# 12_B_TO_B.net
KiCad netlist of a schematic drawn in Altium Designer
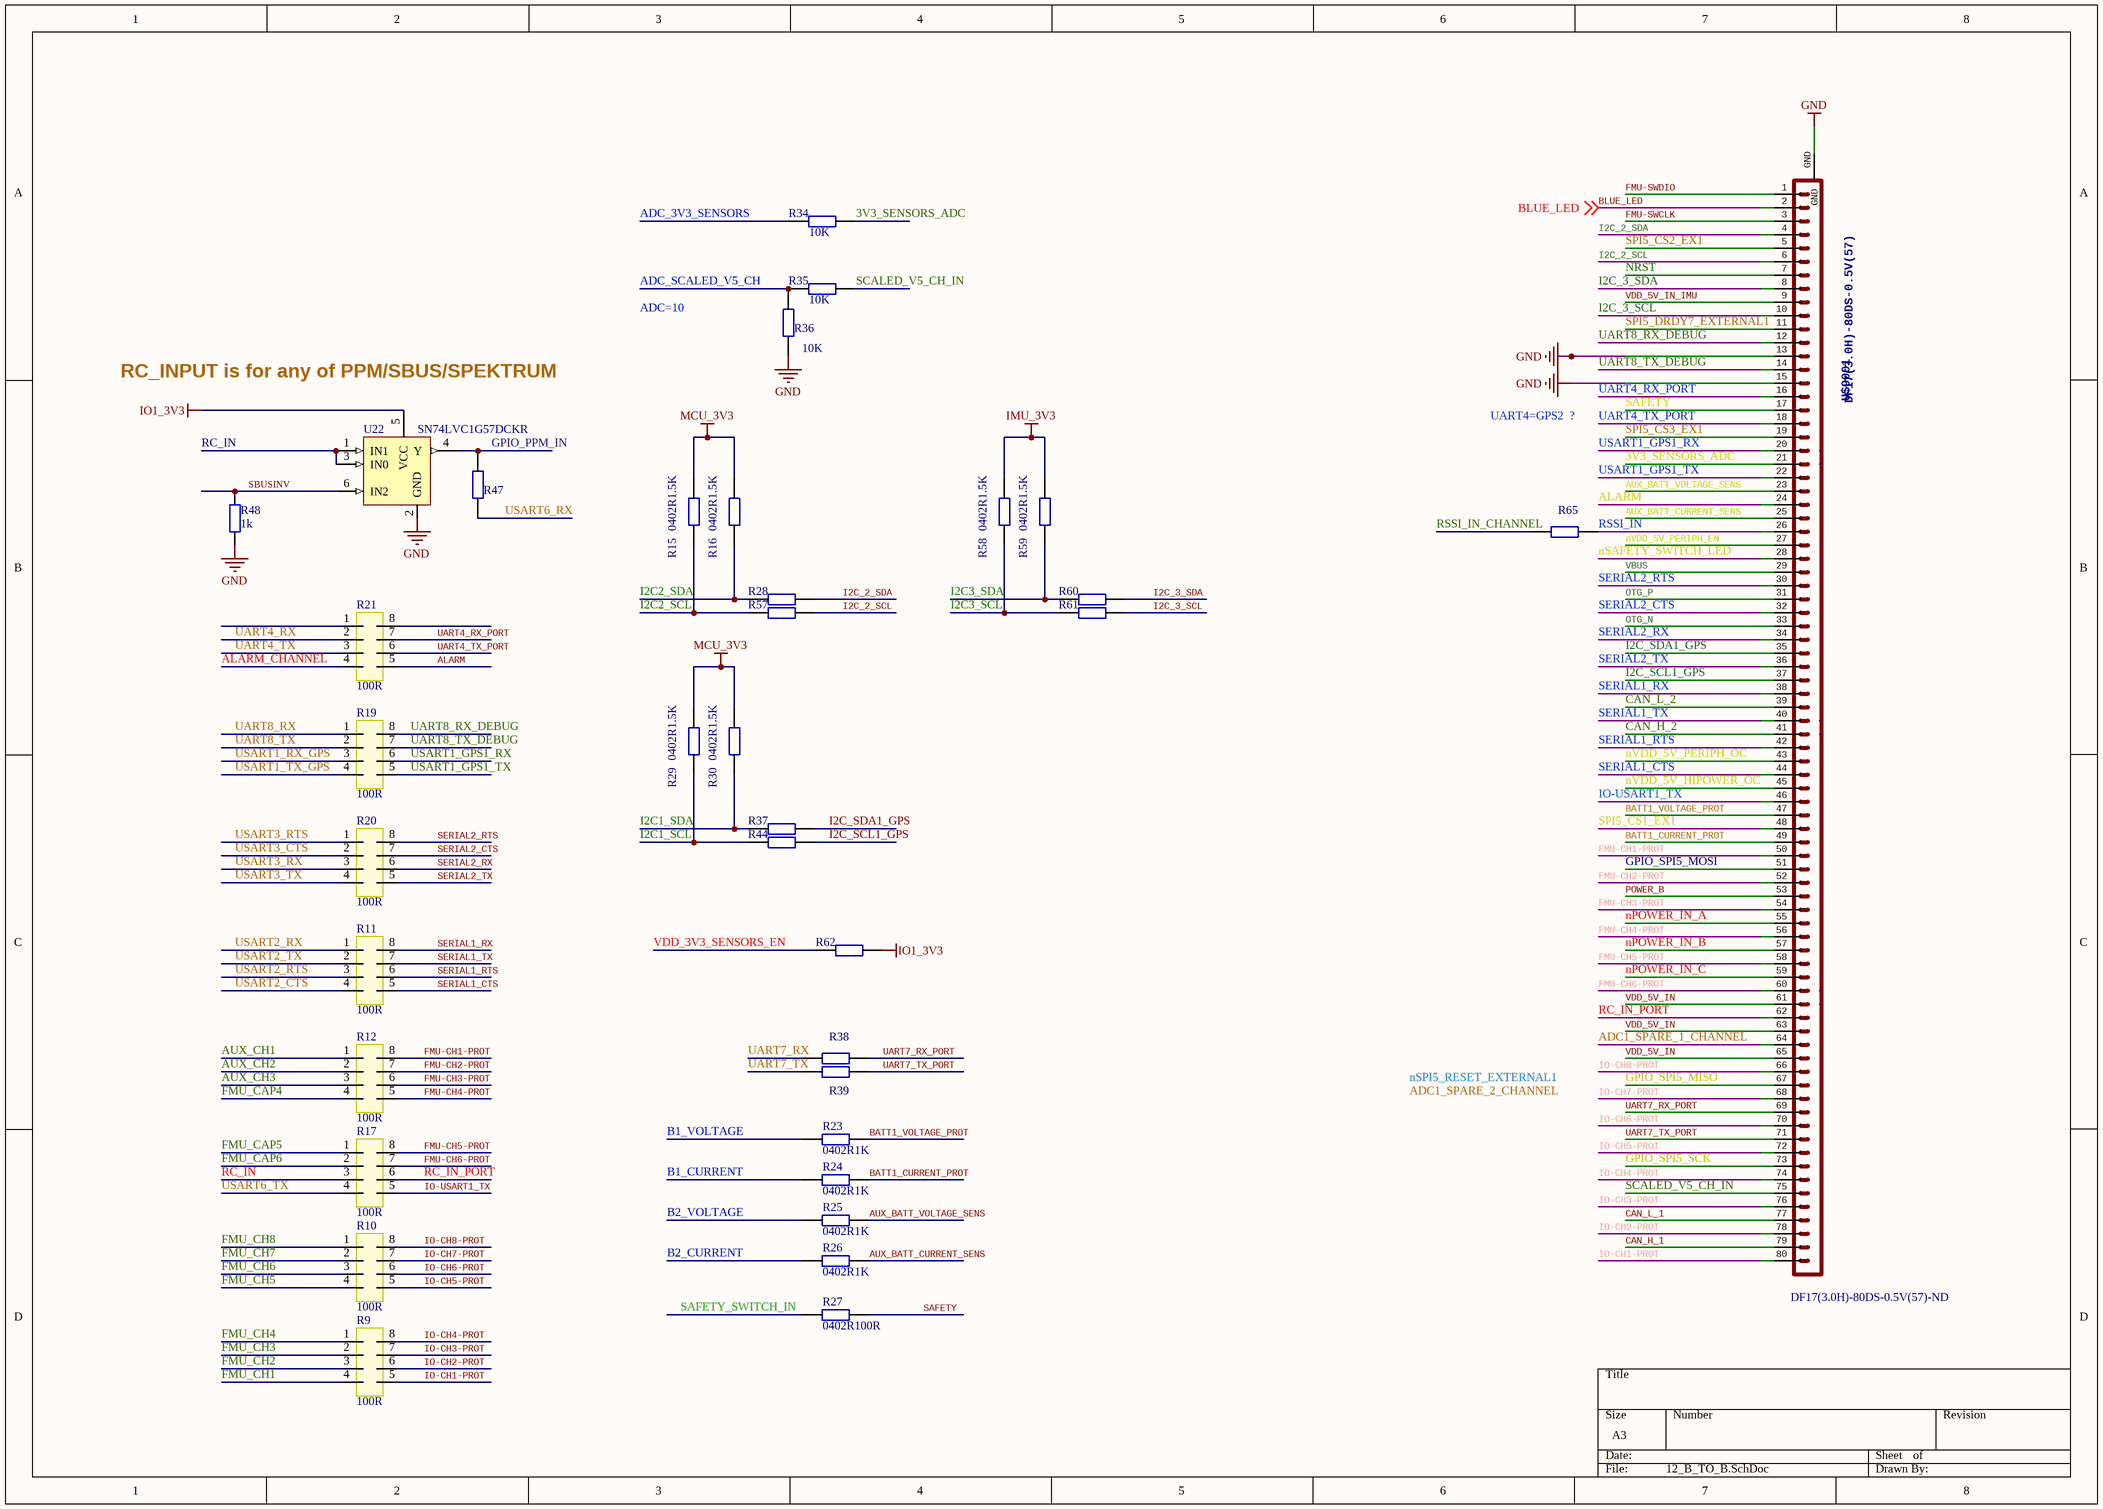
[diagram p0: 12_B_TO_B.SchDoc]

(export (version "E")
  (design (tool "Eeschema 10.0.6"))
  (components
    (comp (ref "R9") (value "100R") (footprint "0402_4r") (libsource (lib "CUAV") (part "0402-8R-4R")))
    (comp (ref "R10") (value "100R") (footprint "0402_4r") (libsource (lib "CUAV") (part "0402-8R-4R")))
    (comp (ref "R11") (value "100R") (footprint "0402_4r") (libsource (lib "CUAV") (part "0402-8R-4R")))
    (comp (ref "R12") (value "100R") (footprint "0402_4r") (libsource (lib "CUAV") (part "0402-8R-4R")))
    (comp (ref "R15")
      (value "0402R1.5K")
      (footprint "0402R")
      (description "0402R10K 1%")
      (libsource (lib "CUAV") (part "0402R10K"))
    )
    (comp (ref "R16")
      (value "0402R1.5K")
      (footprint "0402R")
      (description "0402R10K 1%")
      (libsource (lib "CUAV") (part "0402R10K"))
    )
    (comp (ref "R17") (value "100R") (footprint "0402_4r") (libsource (lib "CUAV") (part "0402-8R-4R")))
    (comp (ref "R19") (value "100R") (footprint "0402_4r") (libsource (lib "CUAV") (part "0402-8R-4R")))
    (comp (ref "R20") (value "100R") (footprint "0402_4r") (libsource (lib "CUAV") (part "0402-8R-4R")))
    (comp (ref "R21") (value "100R") (footprint "0402_4r") (libsource (lib "CUAV") (part "0402-8R-4R")))
    (comp (ref "R23")
      (value "0402R1K")
      (footprint "0402R")
      (description "0402R100R 1%")
      (libsource (lib "CUAV") (part "0402R100R"))
    )
    (comp (ref "R24")
      (value "0402R1K")
      (footprint "0402R")
      (description "0402R100R 1%")
      (libsource (lib "CUAV") (part "0402R100R"))
    )
    (comp (ref "R25")
      (value "0402R1K")
      (footprint "0402R")
      (description "0402R100R 1%")
      (libsource (lib "CUAV") (part "0402R100R"))
    )
    (comp (ref "R26")
      (value "0402R1K")
      (footprint "0402R")
      (description "0402R100R 1%")
      (libsource (lib "CUAV") (part "0402R100R"))
    )
    (comp (ref "R27")
      (value "0402R100R")
      (footprint "0402R")
      (description "0402R100R 1%")
      (libsource (lib "CUAV") (part "0402R100R"))
    )
    (comp (ref "R28")
      (value "0402R100R")
      (footprint "0402R")
      (description "0402R100R 1%")
      (libsource (lib "CUAV") (part "0402R100R"))
    )
    (comp (ref "R29")
      (value "0402R1.5K")
      (footprint "0402R")
      (description "0402R10K 1%")
      (libsource (lib "CUAV") (part "0402R10K"))
    )
    (comp (ref "R30")
      (value "0402R1.5K")
      (footprint "0402R")
      (description "0402R10K 1%")
      (libsource (lib "CUAV") (part "0402R10K"))
    )
    (comp (ref "R34")
      (value "10K")
      (footprint "0402R")
      (description "0402R100R 1%")
      (libsource (lib "CUAV") (part "0402R100R"))
    )
    (comp (ref "R35")
      (value "10K")
      (footprint "0402R")
      (description "0402R100R 1%")
      (libsource (lib "CUAV") (part "0402R100R"))
    )
    (comp (ref "R36")
      (value "10K")
      (footprint "0402R")
      (description "0402R100R 1%")
      (libsource (lib "") (part "0402R100R_1"))
    )
    (comp (ref "R37")
      (value "0402R100R")
      (footprint "0402R")
      (description "0402R100R 1%")
      (libsource (lib "CUAV") (part "0402R100R"))
    )
    (comp (ref "R38")
      (value "0402R100R")
      (footprint "0402R")
      (description "0402R100R 1%")
      (libsource (lib "CUAV") (part "0402R100R"))
    )
    (comp (ref "R39")
      (value "0402R100R")
      (footprint "0402R")
      (description "0402R100R 1%")
      (libsource (lib "CUAV") (part "0402R100R"))
    )
    (comp (ref "R44")
      (value "0402R100R")
      (footprint "0402R")
      (description "0402R100R 1%")
      (libsource (lib "CUAV") (part "0402R100R"))
    )
    (comp (ref "R47")
      (value "100R")
      (footprint "0402R")
      (description "0402R100R 1%")
      (libsource (lib "") (part "0402R100R_1"))
    )
    (comp (ref "R48")
      (value "1k")
      (description "Resistor")
      (fields (field (name "PUBLISHER") "Altium Limited"))
      (libsource (lib "Miscellaneous Devices") (part "Res2"))
    )
    (comp (ref "R57")
      (value "0402R100R")
      (footprint "0402R")
      (description "0402R100R 1%")
      (libsource (lib "CUAV") (part "0402R100R"))
    )
    (comp (ref "R58")
      (value "0402R1.5K")
      (footprint "0402R")
      (description "0402R10K 1%")
      (libsource (lib "CUAV") (part "0402R10K"))
    )
    (comp (ref "R59")
      (value "0402R1.5K")
      (footprint "0402R")
      (description "0402R10K 1%")
      (libsource (lib "CUAV") (part "0402R10K"))
    )
    (comp (ref "R60")
      (value "0402R100R")
      (footprint "0402R")
      (description "0402R100R 1%")
      (libsource (lib "CUAV") (part "0402R100R"))
    )
    (comp (ref "R61")
      (value "0402R100R")
      (footprint "0402R")
      (description "0402R100R 1%")
      (libsource (lib "CUAV") (part "0402R100R"))
    )
    (comp (ref "R62")
      (value "10K/NC")
      (footprint "0402R")
      (description "0402R100R 1%")
      (libsource (lib "CUAV") (part "0402R100R"))
    )
    (comp (ref "R65")
      (value "0402R100R")
      (footprint "0402R")
      (description "0402R100R 1%")
      (libsource (lib "CUAV") (part "0402R100R"))
    )
    (comp (ref "U$9001")
      (value "DF17(3.0H)-80DS-0.5V(57)")
      (footprint "DF17(3.0H)-80DS-0.5V(57)")
      (fields (field (name "SUPPLIER PART NUMBER 1") "DF17(3.0H)-80DS-0.5V(57)-ND"))
      (libsource (lib "altium-import") (part "root_0_CON-DF17-80F_"))
    )
    (comp (ref "U22")
      (value "SN74LVC1G57DCKR")
      (footprint "sot323-6")
      (libsource (lib "My_Altium") (part "74LVC1G57"))
    )
  )
  (nets
    (net (code "1") (name "/3V3_SENSORS_ADC") (class "Default")
      (node (ref "R34") (pin "2") (pintype "passive"))
      (node (ref "U$9001") (pin "21") (pinfunction "21_21") (pintype "passive"))
    )
    (net (code "2") (name "/ADC1_SPARE_1_CHANNEL") (class "Default")
      (node (ref "U$9001") (pin "64") (pinfunction "64_64") (pintype "passive"))
    )
    (net (code "5") (name "/ADC_3V3_SENSORS") (class "Default")
      (node (ref "R34") (pin "1") (pintype "passive"))
    )
    (net (code "6") (name "/ADC_SCALED_V5_CH") (class "Default")
      (node (ref "R35") (pin "1") (pintype "passive"))
      (node (ref "R36") (pin "2") (pintype "passive"))
    )
    (net (code "7") (name "/ALARM") (class "Default")
      (node (ref "R21") (pin "5") (pinfunction "5_5") (pintype "passive"))
      (node (ref "U$9001") (pin "24") (pinfunction "24_24") (pintype "passive"))
    )
    (net (code "8") (name "/ALARM_CHANNEL") (class "Default")
      (node (ref "R21") (pin "4") (pinfunction "4_4") (pintype "passive"))
    )
    (net (code "9") (name "/AUX_BATT_CURRENT_SENS") (class "Default")
      (node (ref "R26") (pin "2") (pintype "passive"))
      (node (ref "U$9001") (pin "25") (pinfunction "25_25") (pintype "passive"))
    )
    (net (code "10") (name "/AUX_BATT_VOLTAGE_SENS") (class "Default")
      (node (ref "R25") (pin "2") (pintype "passive"))
      (node (ref "U$9001") (pin "23") (pinfunction "23_23") (pintype "passive"))
    )
    (net (code "11") (name "/AUX_CH1") (class "Default")
      (node (ref "R12") (pin "1") (pinfunction "1_1") (pintype "passive"))
    )
    (net (code "12") (name "/AUX_CH2") (class "Default")
      (node (ref "R12") (pin "2") (pinfunction "2_2") (pintype "passive"))
    )
    (net (code "13") (name "/AUX_CH3") (class "Default")
      (node (ref "R12") (pin "3") (pinfunction "3_3") (pintype "passive"))
    )
    (net (code "14") (name "/B1_CURRENT") (class "Default") (node (ref "R24") (pin "1") (pintype "passive")))
    (net (code "15") (name "/B1_VOLTAGE") (class "Default") (node (ref "R23") (pin "1") (pintype "passive")))
    (net (code "16") (name "/B2_CURRENT") (class "Default") (node (ref "R26") (pin "1") (pintype "passive")))
    (net (code "17") (name "/B2_VOLTAGE") (class "Default") (node (ref "R25") (pin "1") (pintype "passive")))
    (net (code "18") (name "/BATT1_CURRENT_PROT") (class "Default")
      (node (ref "R24") (pin "2") (pintype "passive"))
      (node (ref "U$9001") (pin "49") (pinfunction "49_49") (pintype "passive"))
    )
    (net (code "19") (name "/BATT1_VOLTAGE_PROT") (class "Default")
      (node (ref "R23") (pin "2") (pintype "passive"))
      (node (ref "U$9001") (pin "47") (pinfunction "47_47") (pintype "passive"))
    )
    (net (code "20") (name "/CAN_H_1") (class "Default")
      (node (ref "U$9001") (pin "79") (pinfunction "79_79") (pintype "passive"))
    )
    (net (code "21") (name "/CAN_H_2") (class "Default")
      (node (ref "U$9001") (pin "41") (pinfunction "41_41") (pintype "passive"))
    )
    (net (code "22") (name "/CAN_L_1") (class "Default")
      (node (ref "U$9001") (pin "77") (pinfunction "77_77") (pintype "passive"))
    )
    (net (code "23") (name "/CAN_L_2") (class "Default")
      (node (ref "U$9001") (pin "39") (pinfunction "39_39") (pintype "passive"))
    )
    (net (code "24") (name "/FMU-CH1-PROT") (class "Default")
      (node (ref "R12") (pin "8") (pinfunction "8_8") (pintype "passive"))
      (node (ref "U$9001") (pin "50") (pinfunction "50_50") (pintype "passive"))
    )
    (net (code "25") (name "/FMU-CH2-PROT") (class "Default")
      (node (ref "R12") (pin "7") (pinfunction "7_7") (pintype "passive"))
      (node (ref "U$9001") (pin "52") (pinfunction "52_52") (pintype "passive"))
    )
    (net (code "26") (name "/FMU-CH3-PROT") (class "Default")
      (node (ref "R12") (pin "6") (pinfunction "6_6") (pintype "passive"))
      (node (ref "U$9001") (pin "54") (pinfunction "54_54") (pintype "passive"))
    )
    (net (code "27") (name "/FMU-CH4-PROT") (class "Default")
      (node (ref "R12") (pin "5") (pinfunction "5_5") (pintype "passive"))
      (node (ref "U$9001") (pin "56") (pinfunction "56_56") (pintype "passive"))
    )
    (net (code "28") (name "/FMU-CH5-PROT") (class "Default")
      (node (ref "R17") (pin "8") (pinfunction "8_8") (pintype "passive"))
      (node (ref "U$9001") (pin "58") (pinfunction "58_58") (pintype "passive"))
    )
    (net (code "29") (name "/FMU-CH6-PROT") (class "Default")
      (node (ref "R17") (pin "7") (pinfunction "7_7") (pintype "passive"))
      (node (ref "U$9001") (pin "60") (pinfunction "60_60") (pintype "passive"))
    )
    (net (code "30") (name "/FMU-SWCLK") (class "Default")
      (node (ref "U$9001") (pin "3") (pinfunction "3_3") (pintype "passive"))
    )
    (net (code "31") (name "/FMU-SWDIO") (class "Default")
      (node (ref "U$9001") (pin "1") (pinfunction "1_1") (pintype "passive"))
    )
    (net (code "32") (name "/FMU_CAP4") (class "Default")
      (node (ref "R12") (pin "4") (pinfunction "4_4") (pintype "passive"))
    )
    (net (code "33") (name "/FMU_CAP5") (class "Default")
      (node (ref "R17") (pin "1") (pinfunction "1_1") (pintype "passive"))
    )
    (net (code "34") (name "/FMU_CAP6") (class "Default")
      (node (ref "R17") (pin "2") (pinfunction "2_2") (pintype "passive"))
    )
    (net (code "35") (name "/FMU_CH1") (class "Default")
      (node (ref "R9") (pin "4") (pinfunction "4_4") (pintype "passive"))
    )
    (net (code "36") (name "/FMU_CH2") (class "Default")
      (node (ref "R9") (pin "3") (pinfunction "3_3") (pintype "passive"))
    )
    (net (code "37") (name "/FMU_CH3") (class "Default")
      (node (ref "R9") (pin "2") (pinfunction "2_2") (pintype "passive"))
    )
    (net (code "38") (name "/FMU_CH4") (class "Default")
      (node (ref "R9") (pin "1") (pinfunction "1_1") (pintype "passive"))
    )
    (net (code "39") (name "/FMU_CH5") (class "Default")
      (node (ref "R10") (pin "4") (pinfunction "4_4") (pintype "passive"))
    )
    (net (code "40") (name "/FMU_CH6") (class "Default")
      (node (ref "R10") (pin "3") (pinfunction "3_3") (pintype "passive"))
    )
    (net (code "41") (name "/FMU_CH7") (class "Default")
      (node (ref "R10") (pin "2") (pinfunction "2_2") (pintype "passive"))
    )
    (net (code "42") (name "/FMU_CH8") (class "Default")
      (node (ref "R10") (pin "1") (pinfunction "1_1") (pintype "passive"))
    )
    (net (code "43") (name "/GPIO_PPM_IN") (class "Default")
      (node (ref "R47") (pin "2") (pintype "passive"))
      (node (ref "U22") (pin "4") (pinfunction "Y_4") (pintype "output"))
    )
    (net (code "44") (name "/GPIO_SPI5_MISO") (class "Default")
      (node (ref "U$9001") (pin "67") (pinfunction "67_67") (pintype "passive"))
    )
    (net (code "45") (name "/GPIO_SPI5_MOSI") (class "Default")
      (node (ref "U$9001") (pin "51") (pinfunction "51_51") (pintype "passive"))
    )
    (net (code "46") (name "/GPIO_SPI5_SCK") (class "Default")
      (node (ref "U$9001") (pin "73") (pinfunction "73_73") (pintype "passive"))
    )
    (net (code "47") (name "/I2C1_SCL") (class "Default")
      (node (ref "R29") (pin "1") (pintype "passive"))
      (node (ref "R44") (pin "1") (pintype "passive"))
    )
    (net (code "48") (name "/I2C1_SDA") (class "Default")
      (node (ref "R30") (pin "1") (pintype "passive"))
      (node (ref "R37") (pin "1") (pintype "passive"))
    )
    (net (code "49") (name "/I2C2_SCL") (class "Default")
      (node (ref "R15") (pin "1") (pintype "passive"))
      (node (ref "R57") (pin "1") (pintype "passive"))
    )
    (net (code "50") (name "/I2C2_SDA") (class "Default")
      (node (ref "R16") (pin "1") (pintype "passive"))
      (node (ref "R28") (pin "1") (pintype "passive"))
    )
    (net (code "51") (name "/I2C3_SCL") (class "Default")
      (node (ref "R58") (pin "1") (pintype "passive"))
      (node (ref "R61") (pin "1") (pintype "passive"))
    )
    (net (code "52") (name "/I2C3_SDA") (class "Default")
      (node (ref "R59") (pin "1") (pintype "passive"))
      (node (ref "R60") (pin "1") (pintype "passive"))
    )
    (net (code "53") (name "/I2C_2_SCL") (class "Default")
      (node (ref "R57") (pin "2") (pintype "passive"))
      (node (ref "U$9001") (pin "6") (pinfunction "6_6") (pintype "passive"))
    )
    (net (code "54") (name "/I2C_2_SDA") (class "Default")
      (node (ref "R28") (pin "2") (pintype "passive"))
      (node (ref "U$9001") (pin "4") (pinfunction "4_4") (pintype "passive"))
    )
    (net (code "55") (name "/I2C_3_SCL") (class "Default")
      (node (ref "R61") (pin "2") (pintype "passive"))
      (node (ref "U$9001") (pin "10") (pinfunction "10_10") (pintype "passive"))
    )
    (net (code "56") (name "/I2C_3_SDA") (class "Default")
      (node (ref "R60") (pin "2") (pintype "passive"))
      (node (ref "U$9001") (pin "8") (pinfunction "8_8") (pintype "passive"))
    )
    (net (code "57") (name "/I2C_SCL1_GPS") (class "Default")
      (node (ref "R44") (pin "2") (pintype "passive"))
      (node (ref "U$9001") (pin "37") (pinfunction "37_37") (pintype "passive"))
    )
    (net (code "58") (name "/I2C_SDA1_GPS") (class "Default")
      (node (ref "R37") (pin "2") (pintype "passive"))
      (node (ref "U$9001") (pin "35") (pinfunction "35_35") (pintype "passive"))
    )
    (net (code "59") (name "/IO-CH1-PROT") (class "Default")
      (node (ref "R9") (pin "5") (pinfunction "5_5") (pintype "passive"))
      (node (ref "U$9001") (pin "80") (pinfunction "80_80") (pintype "passive"))
    )
    (net (code "60") (name "/IO-CH2-PROT") (class "Default")
      (node (ref "R9") (pin "6") (pinfunction "6_6") (pintype "passive"))
      (node (ref "U$9001") (pin "78") (pinfunction "78_78") (pintype "passive"))
    )
    (net (code "61") (name "/IO-CH3-PROT") (class "Default")
      (node (ref "R9") (pin "7") (pinfunction "7_7") (pintype "passive"))
      (node (ref "U$9001") (pin "76") (pinfunction "76_76") (pintype "passive"))
    )
    (net (code "62") (name "/IO-CH4-PROT") (class "Default")
      (node (ref "R9") (pin "8") (pinfunction "8_8") (pintype "passive"))
      (node (ref "U$9001") (pin "74") (pinfunction "74_74") (pintype "passive"))
    )
    (net (code "63") (name "/IO-CH5-PROT") (class "Default")
      (node (ref "R10") (pin "5") (pinfunction "5_5") (pintype "passive"))
      (node (ref "U$9001") (pin "72") (pinfunction "72_72") (pintype "passive"))
    )
    (net (code "64") (name "/IO-CH6-PROT") (class "Default")
      (node (ref "R10") (pin "6") (pinfunction "6_6") (pintype "passive"))
      (node (ref "U$9001") (pin "70") (pinfunction "70_70") (pintype "passive"))
    )
    (net (code "65") (name "/IO-CH7-PROT") (class "Default")
      (node (ref "R10") (pin "7") (pinfunction "7_7") (pintype "passive"))
      (node (ref "U$9001") (pin "68") (pinfunction "68_68") (pintype "passive"))
    )
    (net (code "66") (name "/IO-CH8-PROT") (class "Default")
      (node (ref "R10") (pin "8") (pinfunction "8_8") (pintype "passive"))
      (node (ref "U$9001") (pin "66") (pinfunction "66_66") (pintype "passive"))
    )
    (net (code "67") (name "/IO-USART1_TX") (class "Default")
      (node (ref "R17") (pin "5") (pinfunction "5_5") (pintype "passive"))
      (node (ref "U$9001") (pin "46") (pinfunction "46_46") (pintype "passive"))
    )
    (net (code "68") (name "/NRST") (class "Default")
      (node (ref "U$9001") (pin "7") (pinfunction "7_7") (pintype "passive"))
    )
    (net (code "69") (name "/OTG_N") (class "Default")
      (node (ref "U$9001") (pin "33") (pinfunction "33_33") (pintype "passive"))
    )
    (net (code "70") (name "/OTG_P") (class "Default")
      (node (ref "U$9001") (pin "31") (pinfunction "31_31") (pintype "passive"))
    )
    (net (code "71") (name "/POWER_B") (class "Default")
      (node (ref "U$9001") (pin "53") (pinfunction "53_53") (pintype "passive"))
    )
    (net (code "72") (name "/RC_IN") (class "Default")
      (node (ref "R17") (pin "3") (pinfunction "3_3") (pintype "passive"))
      (node (ref "U22") (pin "1") (pinfunction "IN1_1") (pintype "input"))
      (node (ref "U22") (pin "3") (pinfunction "IN0_3") (pintype "input"))
    )
    (net (code "73") (name "/RC_IN_PORT") (class "Default")
      (node (ref "R17") (pin "6") (pinfunction "6_6") (pintype "passive"))
      (node (ref "U$9001") (pin "62") (pinfunction "62_62") (pintype "passive"))
    )
    (net (code "74") (name "/RSSI_IN") (class "Default")
      (node (ref "R65") (pin "2") (pintype "passive"))
      (node (ref "U$9001") (pin "26") (pinfunction "26_26") (pintype "passive"))
    )
    (net (code "75") (name "/RSSI_IN_CHANNEL") (class "Default")
      (node (ref "R65") (pin "1") (pintype "passive"))
    )
    (net (code "76") (name "/SAFETY") (class "Default")
      (node (ref "R27") (pin "2") (pintype "passive"))
      (node (ref "U$9001") (pin "17") (pinfunction "17_17") (pintype "passive"))
    )
    (net (code "77") (name "/SAFETY_SWITCH_IN") (class "Default")
      (node (ref "R27") (pin "1") (pintype "passive"))
    )
    (net (code "78") (name "/SBUSINV") (class "Default")
      (node (ref "R48") (pin "2") (pinfunction "2_2") (pintype "passive"))
      (node (ref "U22") (pin "6") (pinfunction "IN2_6") (pintype "input"))
    )
    (net (code "79") (name "/SCALED_V5_CH_IN") (class "Default")
      (node (ref "R35") (pin "2") (pintype "passive"))
      (node (ref "U$9001") (pin "75") (pinfunction "75_75") (pintype "passive"))
    )
    (net (code "80") (name "/SERIAL1_CTS") (class "Default")
      (node (ref "R11") (pin "5") (pinfunction "5_5") (pintype "passive"))
      (node (ref "U$9001") (pin "44") (pinfunction "44_44") (pintype "passive"))
    )
    (net (code "81") (name "/SERIAL1_RTS") (class "Default")
      (node (ref "R11") (pin "6") (pinfunction "6_6") (pintype "passive"))
      (node (ref "U$9001") (pin "42") (pinfunction "42_42") (pintype "passive"))
    )
    (net (code "82") (name "/SERIAL1_RX") (class "Default")
      (node (ref "R11") (pin "8") (pinfunction "8_8") (pintype "passive"))
      (node (ref "U$9001") (pin "38") (pinfunction "38_38") (pintype "passive"))
    )
    (net (code "83") (name "/SERIAL1_TX") (class "Default")
      (node (ref "R11") (pin "7") (pinfunction "7_7") (pintype "passive"))
      (node (ref "U$9001") (pin "40") (pinfunction "40_40") (pintype "passive"))
    )
    (net (code "84") (name "/SERIAL2_CTS") (class "Default")
      (node (ref "R20") (pin "7") (pinfunction "7_7") (pintype "passive"))
      (node (ref "U$9001") (pin "32") (pinfunction "32_32") (pintype "passive"))
    )
    (net (code "85") (name "/SERIAL2_RTS") (class "Default")
      (node (ref "R20") (pin "8") (pinfunction "8_8") (pintype "passive"))
      (node (ref "U$9001") (pin "30") (pinfunction "30_30") (pintype "passive"))
    )
    (net (code "86") (name "/SERIAL2_RX") (class "Default")
      (node (ref "R20") (pin "6") (pinfunction "6_6") (pintype "passive"))
      (node (ref "U$9001") (pin "34") (pinfunction "34_34") (pintype "passive"))
    )
    (net (code "87") (name "/SERIAL2_TX") (class "Default")
      (node (ref "R20") (pin "5") (pinfunction "5_5") (pintype "passive"))
      (node (ref "U$9001") (pin "36") (pinfunction "36_36") (pintype "passive"))
    )
    (net (code "88") (name "/SPI5_CS1_EX1") (class "Default")
      (node (ref "U$9001") (pin "48") (pinfunction "48_48") (pintype "passive"))
    )
    (net (code "89") (name "/SPI5_CS2_EX1") (class "Default")
      (node (ref "U$9001") (pin "5") (pinfunction "5_5") (pintype "passive"))
    )
    (net (code "90") (name "/SPI5_CS3_EX1") (class "Default")
      (node (ref "U$9001") (pin "19") (pinfunction "19_19") (pintype "passive"))
    )
    (net (code "91") (name "/SPI5_DRDY7_EXTERNAL1") (class "Default")
      (node (ref "U$9001") (pin "11") (pinfunction "11_11") (pintype "passive"))
    )
    (net (code "93") (name "/UART4_RX") (class "Default")
      (node (ref "R21") (pin "2") (pinfunction "2_2") (pintype "passive"))
    )
    (net (code "94") (name "/UART4_RX_PORT") (class "Default")
      (node (ref "R21") (pin "7") (pinfunction "7_7") (pintype "passive"))
      (node (ref "U$9001") (pin "16") (pinfunction "16_16") (pintype "passive"))
    )
    (net (code "95") (name "/UART4_TX") (class "Default")
      (node (ref "R21") (pin "3") (pinfunction "3_3") (pintype "passive"))
    )
    (net (code "96") (name "/UART4_TX_PORT") (class "Default")
      (node (ref "R21") (pin "6") (pinfunction "6_6") (pintype "passive"))
      (node (ref "U$9001") (pin "18") (pinfunction "18_18") (pintype "passive"))
    )
    (net (code "97") (name "/UART7_RX") (class "Default") (node (ref "R38") (pin "1") (pintype "passive")))
    (net (code "98") (name "/UART7_RX_PORT") (class "Default")
      (node (ref "R38") (pin "2") (pintype "passive"))
      (node (ref "U$9001") (pin "69") (pinfunction "69_69") (pintype "passive"))
    )
    (net (code "99") (name "/UART7_TX") (class "Default") (node (ref "R39") (pin "1") (pintype "passive")))
    (net (code "100") (name "/UART7_TX_PORT") (class "Default")
      (node (ref "R39") (pin "2") (pintype "passive"))
      (node (ref "U$9001") (pin "71") (pinfunction "71_71") (pintype "passive"))
    )
    (net (code "101") (name "/UART8_RX") (class "Default")
      (node (ref "R19") (pin "1") (pinfunction "1_1") (pintype "passive"))
    )
    (net (code "102") (name "/UART8_RX_DEBUG") (class "Default")
      (node (ref "R19") (pin "8") (pinfunction "8_8") (pintype "passive"))
      (node (ref "U$9001") (pin "12") (pinfunction "12_12") (pintype "passive"))
    )
    (net (code "103") (name "/UART8_TX") (class "Default")
      (node (ref "R19") (pin "2") (pinfunction "2_2") (pintype "passive"))
    )
    (net (code "104") (name "/UART8_TX_DEBUG") (class "Default")
      (node (ref "R19") (pin "7") (pinfunction "7_7") (pintype "passive"))
      (node (ref "U$9001") (pin "14") (pinfunction "14_14") (pintype "passive"))
    )
    (net (code "105") (name "/USART1_GPS1_RX") (class "Default")
      (node (ref "R19") (pin "6") (pinfunction "6_6") (pintype "passive"))
      (node (ref "U$9001") (pin "20") (pinfunction "20_20") (pintype "passive"))
    )
    (net (code "106") (name "/USART1_GPS1_TX") (class "Default")
      (node (ref "R19") (pin "5") (pinfunction "5_5") (pintype "passive"))
      (node (ref "U$9001") (pin "22") (pinfunction "22_22") (pintype "passive"))
    )
    (net (code "107") (name "/USART1_RX_GPS") (class "Default")
      (node (ref "R19") (pin "3") (pinfunction "3_3") (pintype "passive"))
    )
    (net (code "108") (name "/USART1_TX_GPS") (class "Default")
      (node (ref "R19") (pin "4") (pinfunction "4_4") (pintype "passive"))
    )
    (net (code "109") (name "/USART2_CTS") (class "Default")
      (node (ref "R11") (pin "4") (pinfunction "4_4") (pintype "passive"))
    )
    (net (code "110") (name "/USART2_RTS") (class "Default")
      (node (ref "R11") (pin "3") (pinfunction "3_3") (pintype "passive"))
    )
    (net (code "111") (name "/USART2_RX") (class "Default")
      (node (ref "R11") (pin "1") (pinfunction "1_1") (pintype "passive"))
    )
    (net (code "112") (name "/USART2_TX") (class "Default")
      (node (ref "R11") (pin "2") (pinfunction "2_2") (pintype "passive"))
    )
    (net (code "113") (name "/USART3_CTS") (class "Default")
      (node (ref "R20") (pin "2") (pinfunction "2_2") (pintype "passive"))
    )
    (net (code "114") (name "/USART3_RTS") (class "Default")
      (node (ref "R20") (pin "1") (pinfunction "1_1") (pintype "passive"))
    )
    (net (code "115") (name "/USART3_RX") (class "Default")
      (node (ref "R20") (pin "3") (pinfunction "3_3") (pintype "passive"))
    )
    (net (code "116") (name "/USART3_TX") (class "Default")
      (node (ref "R20") (pin "4") (pinfunction "4_4") (pintype "passive"))
    )
    (net (code "117") (name "/USART6_RX") (class "Default") (node (ref "R47") (pin "1") (pintype "passive")))
    (net (code "118") (name "/USART6_TX") (class "Default")
      (node (ref "R17") (pin "4") (pinfunction "4_4") (pintype "passive"))
    )
    (net (code "119") (name "/VBUS") (class "Default")
      (node (ref "U$9001") (pin "29") (pinfunction "29_29") (pintype "passive"))
    )
    (net (code "120") (name "/VDD_3V3_SENSORS_EN") (class "Default")
      (node (ref "R62") (pin "1") (pintype "passive"))
    )
    (net (code "121") (name "/VDD_5V_IN") (class "Default")
      (node (ref "U$9001") (pin "61") (pinfunction "61_61") (pintype "passive"))
      (node (ref "U$9001") (pin "63") (pinfunction "63_63") (pintype "passive"))
      (node (ref "U$9001") (pin "65") (pinfunction "65_65") (pintype "passive"))
    )
    (net (code "122") (name "/VDD_5V_IN_IMU") (class "Default")
      (node (ref "U$9001") (pin "9") (pinfunction "9_9") (pintype "passive"))
    )
    (net (code "123") (name "/nPOWER_IN_A") (class "Default")
      (node (ref "U$9001") (pin "55") (pinfunction "55_55") (pintype "passive"))
    )
    (net (code "124") (name "/nPOWER_IN_B") (class "Default")
      (node (ref "U$9001") (pin "57") (pinfunction "57_57") (pintype "passive"))
    )
    (net (code "125") (name "/nPOWER_IN_C") (class "Default")
      (node (ref "U$9001") (pin "59") (pinfunction "59_59") (pintype "passive"))
    )
    (net (code "126") (name "/nSAFETY_SWITCH_LED") (class "Default")
      (node (ref "U$9001") (pin "28") (pinfunction "28_28") (pintype "passive"))
    )
    (net (code "128") (name "/nVDD_5V_HIPOWER_OC") (class "Default")
      (node (ref "U$9001") (pin "45") (pinfunction "45_45") (pintype "passive"))
    )
    (net (code "129") (name "/nVDD_5V_PERIPH_EN") (class "Default")
      (node (ref "U$9001") (pin "27") (pinfunction "27_27") (pintype "passive"))
    )
    (net (code "130") (name "/nVDD_5V_PERIPH_OC") (class "Default")
      (node (ref "U$9001") (pin "43") (pinfunction "43_43") (pintype "passive"))
    )
    (net (code "131") (name "BLUE_LED") (class "Default")
      (node (ref "U$9001") (pin "2") (pinfunction "2_2") (pintype "passive"))
    )
    (net (code "132") (name "GND") (class "Default")
      (node (ref "R36") (pin "1") (pintype "passive"))
      (node (ref "R48") (pin "1") (pinfunction "1_1") (pintype "passive"))
      (node (ref "U$9001") (pin "13") (pinfunction "13_13") (pintype "passive"))
      (node (ref "U$9001") (pin "15") (pinfunction "15_15") (pintype "passive"))
      (node (ref "U$9001") (pin "GND") (pinfunction "GND_GND") (pintype "passive"))
      (node (ref "U22") (pin "2") (pinfunction "GND_2") (pintype "power_in"))
    )
    (net (code "133") (name "IMU_3V3") (class "Default")
      (node (ref "R58") (pin "2") (pintype "passive"))
      (node (ref "R59") (pin "2") (pintype "passive"))
    )
    (net (code "134") (name "IO1_3V3") (class "Default")
      (node (ref "R62") (pin "2") (pintype "passive"))
      (node (ref "U22") (pin "5") (pinfunction "VCC_5") (pintype "power_in"))
    )
    (net (code "135") (name "MCU_3V3") (class "Default")
      (node (ref "R15") (pin "2") (pintype "passive"))
      (node (ref "R16") (pin "2") (pintype "passive"))
      (node (ref "R29") (pin "2") (pintype "passive"))
      (node (ref "R30") (pin "2") (pintype "passive"))
    )
    (net (code "136") (name "unconnected-(R21-Pad1)") (class "Default")
      (node (ref "R21") (pin "1") (pinfunction "1_1") (pintype "passive"))
    )
    (net (code "137") (name "unconnected-(R21-Pad8)") (class "Default")
      (node (ref "R21") (pin "8") (pinfunction "8_8") (pintype "passive"))
    )
  )
)
